# SimpleEMGCircuit.net
KiCad netlist of a schematic drawn in EAGLE
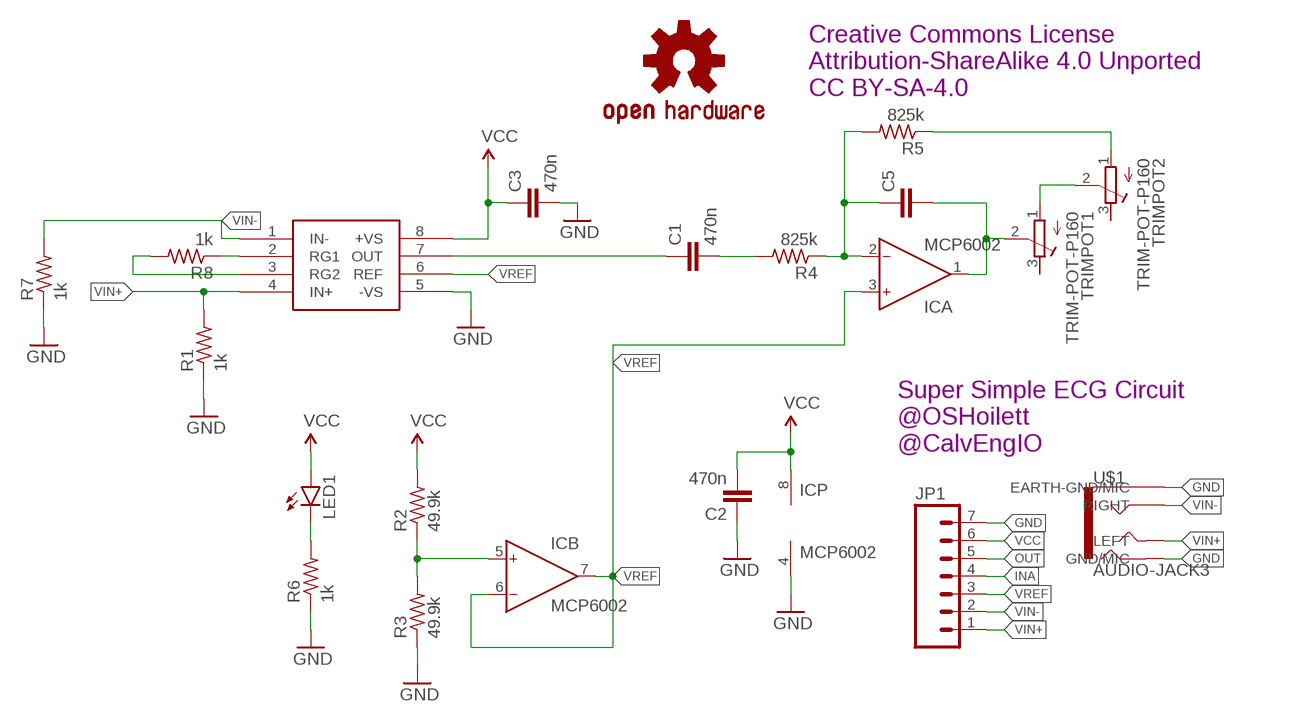
[diagram p0: schematic, sheet 1]

(export (version "E")
  (design (tool "Eeschema 10.0.6"))
  (components
    (comp (ref "C1")
      (value "470n")
      (footprint "eagle-import:C0402")
      (libsource (lib "eagle-import") (part "C-EUC0402"))
    )
    (comp (ref "C2")
      (value "470n")
      (footprint "eagle-import:C0402")
      (libsource (lib "eagle-import") (part "C-EUC0402"))
    )
    (comp (ref "C3")
      (value "470n")
      (footprint "eagle-import:C0402")
      (libsource (lib "eagle-import") (part "C-EUC0402"))
    )
    (comp (ref "C5")
      (value "C-EU025-024X044")
      (footprint "eagle-import:C025-024X044")
      (libsource (lib "eagle-import") (part "C-EU025-024X044"))
    )
    (comp (ref "IC")
      (value "MCP6002")
      (footprint "eagle-import:MSOP08")
      (fields (field (name "MF") "ALTERA CORPORATION") (field (name "MPN") "AD8607ARMZ-REEL"))
      (libsource (lib "eagle-import") (part "AD8607RM"))
    )
    (comp (ref "INA")
      (value "AD8220")
      (footprint "eagle-import:MSOP08")
      (libsource (lib "eagle-import") (part "AD8220"))
    )
    (comp (ref "JP1")
      (value "M07")
      (footprint "eagle-import:1X07")
      (libsource (lib "eagle-import") (part "M07"))
    )
    (comp (ref "LED1")
      (value "LED0603")
      (footprint "eagle-import:LED-0603")
      (libsource (lib "eagle-import") (part "LED0603"))
    )
    (comp (ref "LOGO1")
      (value "OSHW-LOGOS")
      (footprint "eagle-import:OSHW-LOGO-S")
      (libsource (lib "eagle-import") (part "OSHW-LOGOS"))
    )
    (comp (ref "R1")
      (value "1k")
      (footprint "eagle-import:R0402")
      (libsource (lib "eagle-import") (part "R-US_R0402"))
    )
    (comp (ref "R2")
      (value "49.9k")
      (footprint "eagle-import:R0402")
      (libsource (lib "eagle-import") (part "R-US_R0402"))
    )
    (comp (ref "R3")
      (value "49.9k")
      (footprint "eagle-import:R0402")
      (libsource (lib "eagle-import") (part "R-US_R0402"))
    )
    (comp (ref "R4")
      (value "825k")
      (footprint "eagle-import:R0402")
      (libsource (lib "eagle-import") (part "R-US_R0402"))
    )
    (comp (ref "R5")
      (value "825k")
      (footprint "eagle-import:R0402")
      (libsource (lib "eagle-import") (part "R-US_R0402"))
    )
    (comp (ref "R6")
      (value "1k")
      (footprint "eagle-import:R0402")
      (libsource (lib "eagle-import") (part "R-US_R0402"))
    )
    (comp (ref "R7")
      (value "1k")
      (footprint "eagle-import:R0402")
      (libsource (lib "eagle-import") (part "R-US_R0402"))
    )
    (comp (ref "R8")
      (value "1k")
      (footprint "eagle-import:R0402")
      (libsource (lib "eagle-import") (part "R-US_R0402"))
    )
    (comp (ref "TRIMPOT1")
      (value "TRIM-POT-P160")
      (footprint "eagle-import:16MMROTARYPOT")
      (libsource (lib "eagle-import") (part "TRIM-POT-P160"))
    )
    (comp (ref "TRIMPOT2")
      (value "TRIM-POT-P160")
      (footprint "eagle-import:16MMROTARYPOT")
      (libsource (lib "eagle-import") (part "TRIM-POT-P160"))
    )
    (comp (ref "U$1")
      (value "AUDIO-JACK3")
      (footprint "eagle-import:AUDIO-JACK-TRRS-SMD")
      (libsource (lib "eagle-import") (part "AUDIO-JACK3"))
    )
  )
  (nets
    (net (code "1") (name "GND") (class "Default")
      (node (ref "C2") (pin "1") (pinfunction "1_1") (pintype "passive"))
      (node (ref "C3") (pin "2") (pinfunction "2_2") (pintype "passive"))
      (node (ref "IC") (pin "4") (pinfunction "V-_4") (pintype "power_in"))
      (node (ref "INA") (pin "5") (pinfunction "-VS_5") (pintype "bidirectional"))
      (node (ref "JP1") (pin "7") (pinfunction "7_7") (pintype "passive"))
      (node (ref "R1") (pin "1") (pinfunction "1_1") (pintype "passive"))
      (node (ref "R3") (pin "1") (pinfunction "1_1") (pintype "passive"))
      (node (ref "R6") (pin "1") (pinfunction "1_1") (pintype "passive"))
      (node (ref "R7") (pin "1") (pinfunction "1_1") (pintype "passive"))
      (node (ref "U$1") (pin "EARTH") (pinfunction "EARTH-GND/MIC_EARTH") (pintype "bidirectional"))
      (node (ref "U$1") (pin "RING2") (pinfunction "GND/MIC_RING2") (pintype "bidirectional"))
    )
    (net (code "2") (name "INA") (class "Default")
      (node (ref "C1") (pin "1") (pinfunction "1_1") (pintype "passive"))
      (node (ref "INA") (pin "7") (pinfunction "OUT_7") (pintype "bidirectional"))
      (node (ref "JP1") (pin "4") (pinfunction "4_4") (pintype "passive"))
    )
    (net (code "3") (name "Net-(C1-Pad2)") (class "Default")
      (node (ref "C1") (pin "2") (pinfunction "2_2") (pintype "passive"))
      (node (ref "R4") (pin "2") (pinfunction "2_2") (pintype "passive"))
    )
    (net (code "4") (name "Net-(ICA-IN-)") (class "Default")
      (node (ref "C5") (pin "1") (pinfunction "1_1") (pintype "passive"))
      (node (ref "IC") (pin "2") (pinfunction "IN-_2") (pintype "input"))
      (node (ref "R4") (pin "1") (pinfunction "1_1") (pintype "passive"))
      (node (ref "R5") (pin "2") (pinfunction "2_2") (pintype "passive"))
    )
    (net (code "5") (name "Net-(ICB-IN+)") (class "Default")
      (node (ref "IC") (pin "5") (pinfunction "IN+_5") (pintype "input"))
      (node (ref "R2") (pin "1") (pinfunction "1_1") (pintype "passive"))
      (node (ref "R3") (pin "2") (pinfunction "2_2") (pintype "passive"))
    )
    (net (code "6") (name "Net-(INA-RG1)") (class "Default")
      (node (ref "INA") (pin "2") (pinfunction "RG1_2") (pintype "bidirectional"))
      (node (ref "R8") (pin "1") (pinfunction "1_1") (pintype "passive"))
    )
    (net (code "7") (name "Net-(INA-RG2)") (class "Default")
      (node (ref "INA") (pin "3") (pinfunction "RG2_3") (pintype "bidirectional"))
      (node (ref "R8") (pin "2") (pinfunction "2_2") (pintype "passive"))
    )
    (net (code "8") (name "Net-(LED1-PadC)") (class "Default")
      (node (ref "LED1") (pin "C") (pinfunction "C_C") (pintype "passive"))
      (node (ref "R6") (pin "2") (pinfunction "2_2") (pintype "passive"))
    )
    (net (code "9") (name "Net-(TRIMPOT1-A)") (class "Default")
      (node (ref "TRIMPOT1") (pin "1") (pinfunction "A_1") (pintype "passive"))
      (node (ref "TRIMPOT2") (pin "2") (pinfunction "S_2") (pintype "passive"))
    )
    (net (code "10") (name "Net-(TRIMPOT2-A)") (class "Default")
      (node (ref "R5") (pin "1") (pinfunction "1_1") (pintype "passive"))
      (node (ref "TRIMPOT2") (pin "1") (pinfunction "A_1") (pintype "passive"))
    )
    (net (code "11") (name "OUT") (class "Default")
      (node (ref "C5") (pin "2") (pinfunction "2_2") (pintype "passive"))
      (node (ref "IC") (pin "1") (pinfunction "OUT_1") (pintype "output"))
      (node (ref "JP1") (pin "5") (pinfunction "5_5") (pintype "passive"))
      (node (ref "TRIMPOT1") (pin "2") (pinfunction "S_2") (pintype "passive"))
    )
    (net (code "12") (name "VCC") (class "Default")
      (node (ref "C2") (pin "2") (pinfunction "2_2") (pintype "passive"))
      (node (ref "C3") (pin "1") (pinfunction "1_1") (pintype "passive"))
      (node (ref "IC") (pin "8") (pinfunction "V+_8") (pintype "power_in"))
      (node (ref "INA") (pin "8") (pinfunction "+VS_8") (pintype "bidirectional"))
      (node (ref "JP1") (pin "6") (pinfunction "6_6") (pintype "passive"))
      (node (ref "LED1") (pin "A") (pinfunction "A_A") (pintype "passive"))
      (node (ref "R2") (pin "2") (pinfunction "2_2") (pintype "passive"))
    )
    (net (code "13") (name "VIN+") (class "Default")
      (node (ref "INA") (pin "4") (pinfunction "IN+_4") (pintype "bidirectional"))
      (node (ref "JP1") (pin "1") (pinfunction "1_1") (pintype "passive"))
      (node (ref "R1") (pin "2") (pinfunction "2_2") (pintype "passive"))
      (node (ref "U$1") (pin "TIP") (pinfunction "LEFT_TIP") (pintype "bidirectional"))
    )
    (net (code "14") (name "VIN-") (class "Default")
      (node (ref "INA") (pin "1") (pinfunction "IN-_1") (pintype "bidirectional"))
      (node (ref "JP1") (pin "2") (pinfunction "2_2") (pintype "passive"))
      (node (ref "R7") (pin "2") (pinfunction "2_2") (pintype "passive"))
      (node (ref "U$1") (pin "RING1") (pinfunction "RIGHT_RING1") (pintype "bidirectional"))
    )
    (net (code "15") (name "VREF") (class "Default")
      (node (ref "IC") (pin "3") (pinfunction "IN+_3") (pintype "input"))
      (node (ref "IC") (pin "6") (pinfunction "IN-_6") (pintype "input"))
      (node (ref "IC") (pin "7") (pinfunction "OUT_7") (pintype "output"))
      (node (ref "INA") (pin "6") (pinfunction "REF_6") (pintype "bidirectional"))
      (node (ref "JP1") (pin "3") (pinfunction "3_3") (pintype "passive"))
    )
    (net (code "16") (name "unconnected-(TRIMPOT1-E-Pad3)") (class "Default")
      (node (ref "TRIMPOT1") (pin "3") (pinfunction "E_3") (pintype "passive"))
    )
    (net (code "17") (name "unconnected-(TRIMPOT2-E-Pad3)") (class "Default")
      (node (ref "TRIMPOT2") (pin "3") (pinfunction "E_3") (pintype "passive"))
    )
  )
)
